# zero_board.net
KiCad netlist of a schematic drawn in EAGLE
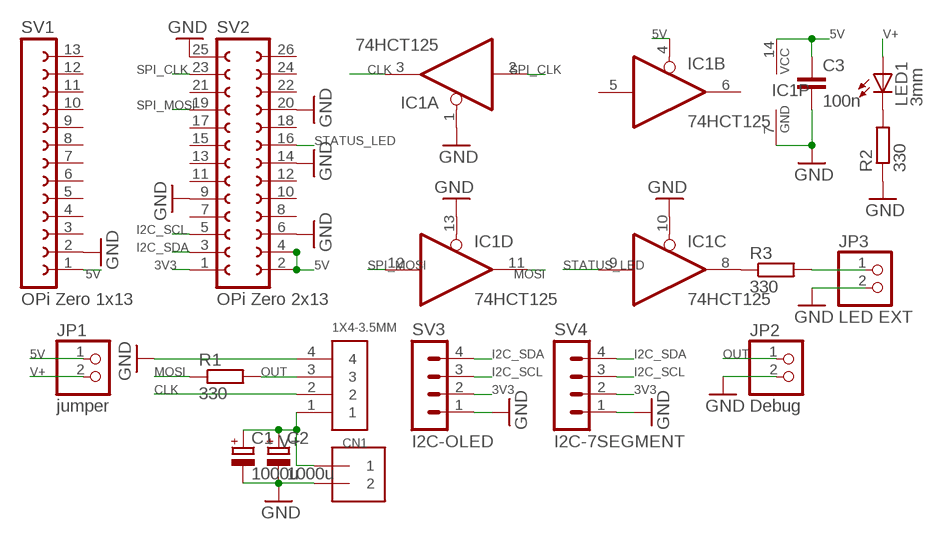
[diagram p0: schematic, sheet 1]

(export (version "E")
  (design (tool "Eeschema 10.0.6"))
  (components
    (comp (ref "C1")
      (value "1000u")
      (footprint "eagle-import:E5-6")
      (libsource (lib "eagle-import") (part "CPOL-EUE5-6"))
    )
    (comp (ref "C2")
      (value "1000u")
      (footprint "eagle-import:E5-6")
      (libsource (lib "eagle-import") (part "CPOL-EUE5-6"))
    )
    (comp (ref "C3")
      (value "100n")
      (footprint "eagle-import:C050-024X044")
      (libsource (lib "eagle-import") (part "C-EU050-024X044"))
    )
    (comp (ref "CN1")
      (value "1X4-3.5MM")
      (footprint "eagle-import:1X04-3.5MM")
      (libsource (lib "eagle-import") (part "1X4-3.5MM"))
    )
    (comp (ref "IC1")
      (value "74HCT125")
      (footprint "eagle-import:SO14")
      (libsource (lib "eagle-import") (part "74125DHCT"))
    )
    (comp (ref "J1")
      (value "1X2-3.5MM")
      (footprint "eagle-import:1X2-3.5MM")
      (libsource (lib "eagle-import") (part "1X2-3.5MM"))
    )
    (comp (ref "JP1")
      (value "jumper")
      (footprint "eagle-import:1X02")
      (libsource (lib "eagle-import") (part "PINHD-1X2"))
    )
    (comp (ref "JP2")
      (value "Debug")
      (footprint "eagle-import:1X02")
      (libsource (lib "eagle-import") (part "PINHD-1X2"))
    )
    (comp (ref "JP3")
      (value "LED EXT")
      (footprint "eagle-import:1X02")
      (libsource (lib "eagle-import") (part "PINHD-1X2"))
    )
    (comp (ref "LED1")
      (value "3mm")
      (footprint "eagle-import:LED3MM")
      (libsource (lib "eagle-import") (part "LED3MM"))
    )
    (comp (ref "R1")
      (value "330")
      (footprint "eagle-import:R0805")
      (libsource (lib "eagle-import") (part "R-EU_R0805"))
    )
    (comp (ref "R2")
      (value "330")
      (footprint "eagle-import:R0805")
      (libsource (lib "eagle-import") (part "R-EU_R0805"))
    )
    (comp (ref "R3")
      (value "330")
      (footprint "eagle-import:R0805")
      (libsource (lib "eagle-import") (part "R-EU_R0805"))
    )
    (comp (ref "SV1")
      (value "OPi Zero 1x13")
      (footprint "eagle-import:FE13")
      (libsource (lib "eagle-import") (part "FE13-1"))
    )
    (comp (ref "SV2")
      (value "OPi Zero 2x13")
      (footprint "eagle-import:FE13-2")
      (libsource (lib "eagle-import") (part "FE13-2"))
    )
    (comp (ref "SV3")
      (value "I2C-OLED")
      (footprint "eagle-import:MA04-1")
      (libsource (lib "eagle-import") (part "MA04-1"))
    )
    (comp (ref "SV4")
      (value "I2C-7SEGMENT")
      (footprint "eagle-import:MA04-1")
      (libsource (lib "eagle-import") (part "MA04-1"))
    )
  )
  (nets
    (net (code "1") (name "/3V3") (class "Default")
      (node (ref "SV2") (pin "1") (pinfunction "1_1") (pintype "passive"))
      (node (ref "SV3") (pin "2") (pinfunction "2_2") (pintype "passive"))
      (node (ref "SV4") (pin "2") (pinfunction "2_2") (pintype "passive"))
    )
    (net (code "2") (name "/5V") (class "Default")
      (node (ref "C3") (pin "1") (pinfunction "1_1") (pintype "passive"))
      (node (ref "IC1") (pin "14") (pinfunction "VCC_14") (pintype "power_in"))
      (node (ref "IC1") (pin "4") (pinfunction "OE_4") (pintype "input"))
      (node (ref "JP1") (pin "1") (pinfunction "1_1") (pintype "passive"))
      (node (ref "SV1") (pin "1") (pinfunction "1_1") (pintype "passive"))
      (node (ref "SV2") (pin "2") (pinfunction "2_2") (pintype "passive"))
      (node (ref "SV2") (pin "4") (pinfunction "4_4") (pintype "passive"))
    )
    (net (code "3") (name "/CLK") (class "Default")
      (node (ref "CN1") (pin "2") (pinfunction "2_2") (pintype "bidirectional"))
      (node (ref "IC1") (pin "3") (pinfunction "O_3") (pintype "tri_state"))
    )
    (net (code "4") (name "/I2C_SCL") (class "Default")
      (node (ref "SV2") (pin "5") (pinfunction "5_5") (pintype "passive"))
      (node (ref "SV3") (pin "3") (pinfunction "3_3") (pintype "passive"))
      (node (ref "SV4") (pin "3") (pinfunction "3_3") (pintype "passive"))
    )
    (net (code "5") (name "/I2C_SDA") (class "Default")
      (node (ref "SV2") (pin "3") (pinfunction "3_3") (pintype "passive"))
      (node (ref "SV3") (pin "4") (pinfunction "4_4") (pintype "passive"))
      (node (ref "SV4") (pin "4") (pinfunction "4_4") (pintype "passive"))
    )
    (net (code "6") (name "/MOSI") (class "Default")
      (node (ref "IC1") (pin "11") (pinfunction "O_11") (pintype "tri_state"))
      (node (ref "R1") (pin "1") (pinfunction "1_1") (pintype "passive"))
    )
    (net (code "7") (name "/OUT") (class "Default")
      (node (ref "CN1") (pin "3") (pinfunction "3_3") (pintype "bidirectional"))
      (node (ref "JP2") (pin "1") (pinfunction "1_1") (pintype "passive"))
      (node (ref "R1") (pin "2") (pinfunction "2_2") (pintype "passive"))
    )
    (net (code "8") (name "/SPI_CLK") (class "Default")
      (node (ref "IC1") (pin "2") (pinfunction "I_2") (pintype "input"))
      (node (ref "SV2") (pin "23") (pinfunction "23_23") (pintype "passive"))
    )
    (net (code "9") (name "/SPI_MOSI") (class "Default")
      (node (ref "IC1") (pin "12") (pinfunction "I_12") (pintype "input"))
      (node (ref "SV2") (pin "19") (pinfunction "19_19") (pintype "passive"))
    )
    (net (code "10") (name "/STATUS_LED") (class "Default")
      (node (ref "IC1") (pin "9") (pinfunction "I_9") (pintype "input"))
      (node (ref "SV2") (pin "16") (pinfunction "16_16") (pintype "passive"))
    )
    (net (code "11") (name "/V+") (class "Default")
      (node (ref "C1") (pin "+") (pinfunction "+_+") (pintype "passive"))
      (node (ref "C2") (pin "+") (pinfunction "+_+") (pintype "passive"))
      (node (ref "CN1") (pin "1") (pinfunction "1_1") (pintype "bidirectional"))
      (node (ref "J1") (pin "1") (pinfunction "1_1") (pintype "passive"))
      (node (ref "JP1") (pin "2") (pinfunction "2_2") (pintype "passive"))
      (node (ref "LED1") (pin "A") (pinfunction "A_A") (pintype "passive"))
    )
    (net (code "12") (name "GND") (class "Default")
      (node (ref "C1") (pin "-") (pinfunction "-_-") (pintype "passive"))
      (node (ref "C2") (pin "-") (pinfunction "-_-") (pintype "passive"))
      (node (ref "C3") (pin "2") (pinfunction "2_2") (pintype "passive"))
      (node (ref "CN1") (pin "4") (pinfunction "4_4") (pintype "bidirectional"))
      (node (ref "IC1") (pin "1") (pinfunction "OE_1") (pintype "input"))
      (node (ref "IC1") (pin "10") (pinfunction "OE_10") (pintype "input"))
      (node (ref "IC1") (pin "13") (pinfunction "OE_13") (pintype "input"))
      (node (ref "IC1") (pin "7") (pinfunction "GND_7") (pintype "power_in"))
      (node (ref "J1") (pin "2") (pinfunction "2_2") (pintype "passive"))
      (node (ref "JP2") (pin "2") (pinfunction "2_2") (pintype "passive"))
      (node (ref "JP3") (pin "2") (pinfunction "2_2") (pintype "passive"))
      (node (ref "R2") (pin "1") (pinfunction "1_1") (pintype "passive"))
      (node (ref "SV1") (pin "2") (pinfunction "2_2") (pintype "passive"))
      (node (ref "SV2") (pin "14") (pinfunction "14_14") (pintype "passive"))
      (node (ref "SV2") (pin "20") (pinfunction "20_20") (pintype "passive"))
      (node (ref "SV2") (pin "25") (pinfunction "25_25") (pintype "passive"))
      (node (ref "SV2") (pin "6") (pinfunction "6_6") (pintype "passive"))
      (node (ref "SV2") (pin "9") (pinfunction "9_9") (pintype "passive"))
      (node (ref "SV3") (pin "1") (pinfunction "1_1") (pintype "passive"))
      (node (ref "SV4") (pin "1") (pinfunction "1_1") (pintype "passive"))
    )
    (net (code "13") (name "Net-(IC1C-O)") (class "Default")
      (node (ref "IC1") (pin "8") (pinfunction "O_8") (pintype "tri_state"))
      (node (ref "R3") (pin "1") (pinfunction "1_1") (pintype "passive"))
    )
    (net (code "14") (name "Net-(JP3-Pad1)") (class "Default")
      (node (ref "JP3") (pin "1") (pinfunction "1_1") (pintype "passive"))
      (node (ref "R3") (pin "2") (pinfunction "2_2") (pintype "passive"))
    )
    (net (code "15") (name "Net-(LED1-C)") (class "Default")
      (node (ref "LED1") (pin "K") (pinfunction "C_K") (pintype "passive"))
      (node (ref "R2") (pin "2") (pinfunction "2_2") (pintype "passive"))
    )
    (net (code "16") (name "unconnected-(IC1B-I-Pad5)") (class "Default")
      (node (ref "IC1") (pin "5") (pinfunction "I_5") (pintype "input"))
    )
    (net (code "17") (name "unconnected-(IC1B-O-Pad6)") (class "Default")
      (node (ref "IC1") (pin "6") (pinfunction "O_6") (pintype "tri_state"))
    )
    (net (code "18") (name "unconnected-(SV1-Pad3)") (class "Default")
      (node (ref "SV1") (pin "3") (pinfunction "3_3") (pintype "passive"))
    )
    (net (code "19") (name "unconnected-(SV1-Pad4)") (class "Default")
      (node (ref "SV1") (pin "4") (pinfunction "4_4") (pintype "passive"))
    )
    (net (code "20") (name "unconnected-(SV1-Pad5)") (class "Default")
      (node (ref "SV1") (pin "5") (pinfunction "5_5") (pintype "passive"))
    )
    (net (code "21") (name "unconnected-(SV1-Pad6)") (class "Default")
      (node (ref "SV1") (pin "6") (pinfunction "6_6") (pintype "passive"))
    )
    (net (code "22") (name "unconnected-(SV1-Pad7)") (class "Default")
      (node (ref "SV1") (pin "7") (pinfunction "7_7") (pintype "passive"))
    )
    (net (code "23") (name "unconnected-(SV1-Pad8)") (class "Default")
      (node (ref "SV1") (pin "8") (pinfunction "8_8") (pintype "passive"))
    )
    (net (code "24") (name "unconnected-(SV1-Pad9)") (class "Default")
      (node (ref "SV1") (pin "9") (pinfunction "9_9") (pintype "passive"))
    )
    (net (code "25") (name "unconnected-(SV1-Pad10)") (class "Default")
      (node (ref "SV1") (pin "10") (pinfunction "10_10") (pintype "passive"))
    )
    (net (code "26") (name "unconnected-(SV1-Pad11)") (class "Default")
      (node (ref "SV1") (pin "11") (pinfunction "11_11") (pintype "passive"))
    )
    (net (code "27") (name "unconnected-(SV1-Pad12)") (class "Default")
      (node (ref "SV1") (pin "12") (pinfunction "12_12") (pintype "passive"))
    )
    (net (code "28") (name "unconnected-(SV1-Pad13)") (class "Default")
      (node (ref "SV1") (pin "13") (pinfunction "13_13") (pintype "passive"))
    )
    (net (code "29") (name "unconnected-(SV2-Pad7)") (class "Default")
      (node (ref "SV2") (pin "7") (pinfunction "7_7") (pintype "passive"))
    )
    (net (code "30") (name "unconnected-(SV2-Pad8)") (class "Default")
      (node (ref "SV2") (pin "8") (pinfunction "8_8") (pintype "passive"))
    )
    (net (code "31") (name "unconnected-(SV2-Pad10)") (class "Default")
      (node (ref "SV2") (pin "10") (pinfunction "10_10") (pintype "passive"))
    )
    (net (code "32") (name "unconnected-(SV2-Pad11)") (class "Default")
      (node (ref "SV2") (pin "11") (pinfunction "11_11") (pintype "passive"))
    )
    (net (code "33") (name "unconnected-(SV2-Pad12)") (class "Default")
      (node (ref "SV2") (pin "12") (pinfunction "12_12") (pintype "passive"))
    )
    (net (code "34") (name "unconnected-(SV2-Pad13)") (class "Default")
      (node (ref "SV2") (pin "13") (pinfunction "13_13") (pintype "passive"))
    )
    (net (code "35") (name "unconnected-(SV2-Pad15)") (class "Default")
      (node (ref "SV2") (pin "15") (pinfunction "15_15") (pintype "passive"))
    )
    (net (code "36") (name "unconnected-(SV2-Pad17)") (class "Default")
      (node (ref "SV2") (pin "17") (pinfunction "17_17") (pintype "passive"))
    )
    (net (code "37") (name "unconnected-(SV2-Pad18)") (class "Default")
      (node (ref "SV2") (pin "18") (pinfunction "18_18") (pintype "passive"))
    )
    (net (code "38") (name "unconnected-(SV2-Pad21)") (class "Default")
      (node (ref "SV2") (pin "21") (pinfunction "21_21") (pintype "passive"))
    )
    (net (code "39") (name "unconnected-(SV2-Pad22)") (class "Default")
      (node (ref "SV2") (pin "22") (pinfunction "22_22") (pintype "passive"))
    )
    (net (code "40") (name "unconnected-(SV2-Pad24)") (class "Default")
      (node (ref "SV2") (pin "24") (pinfunction "24_24") (pintype "passive"))
    )
    (net (code "41") (name "unconnected-(SV2-Pad26)") (class "Default")
      (node (ref "SV2") (pin "26") (pinfunction "26_26") (pintype "passive"))
    )
  )
)
